# astabil.net
KiCad netlist of a schematic drawn in EAGLE
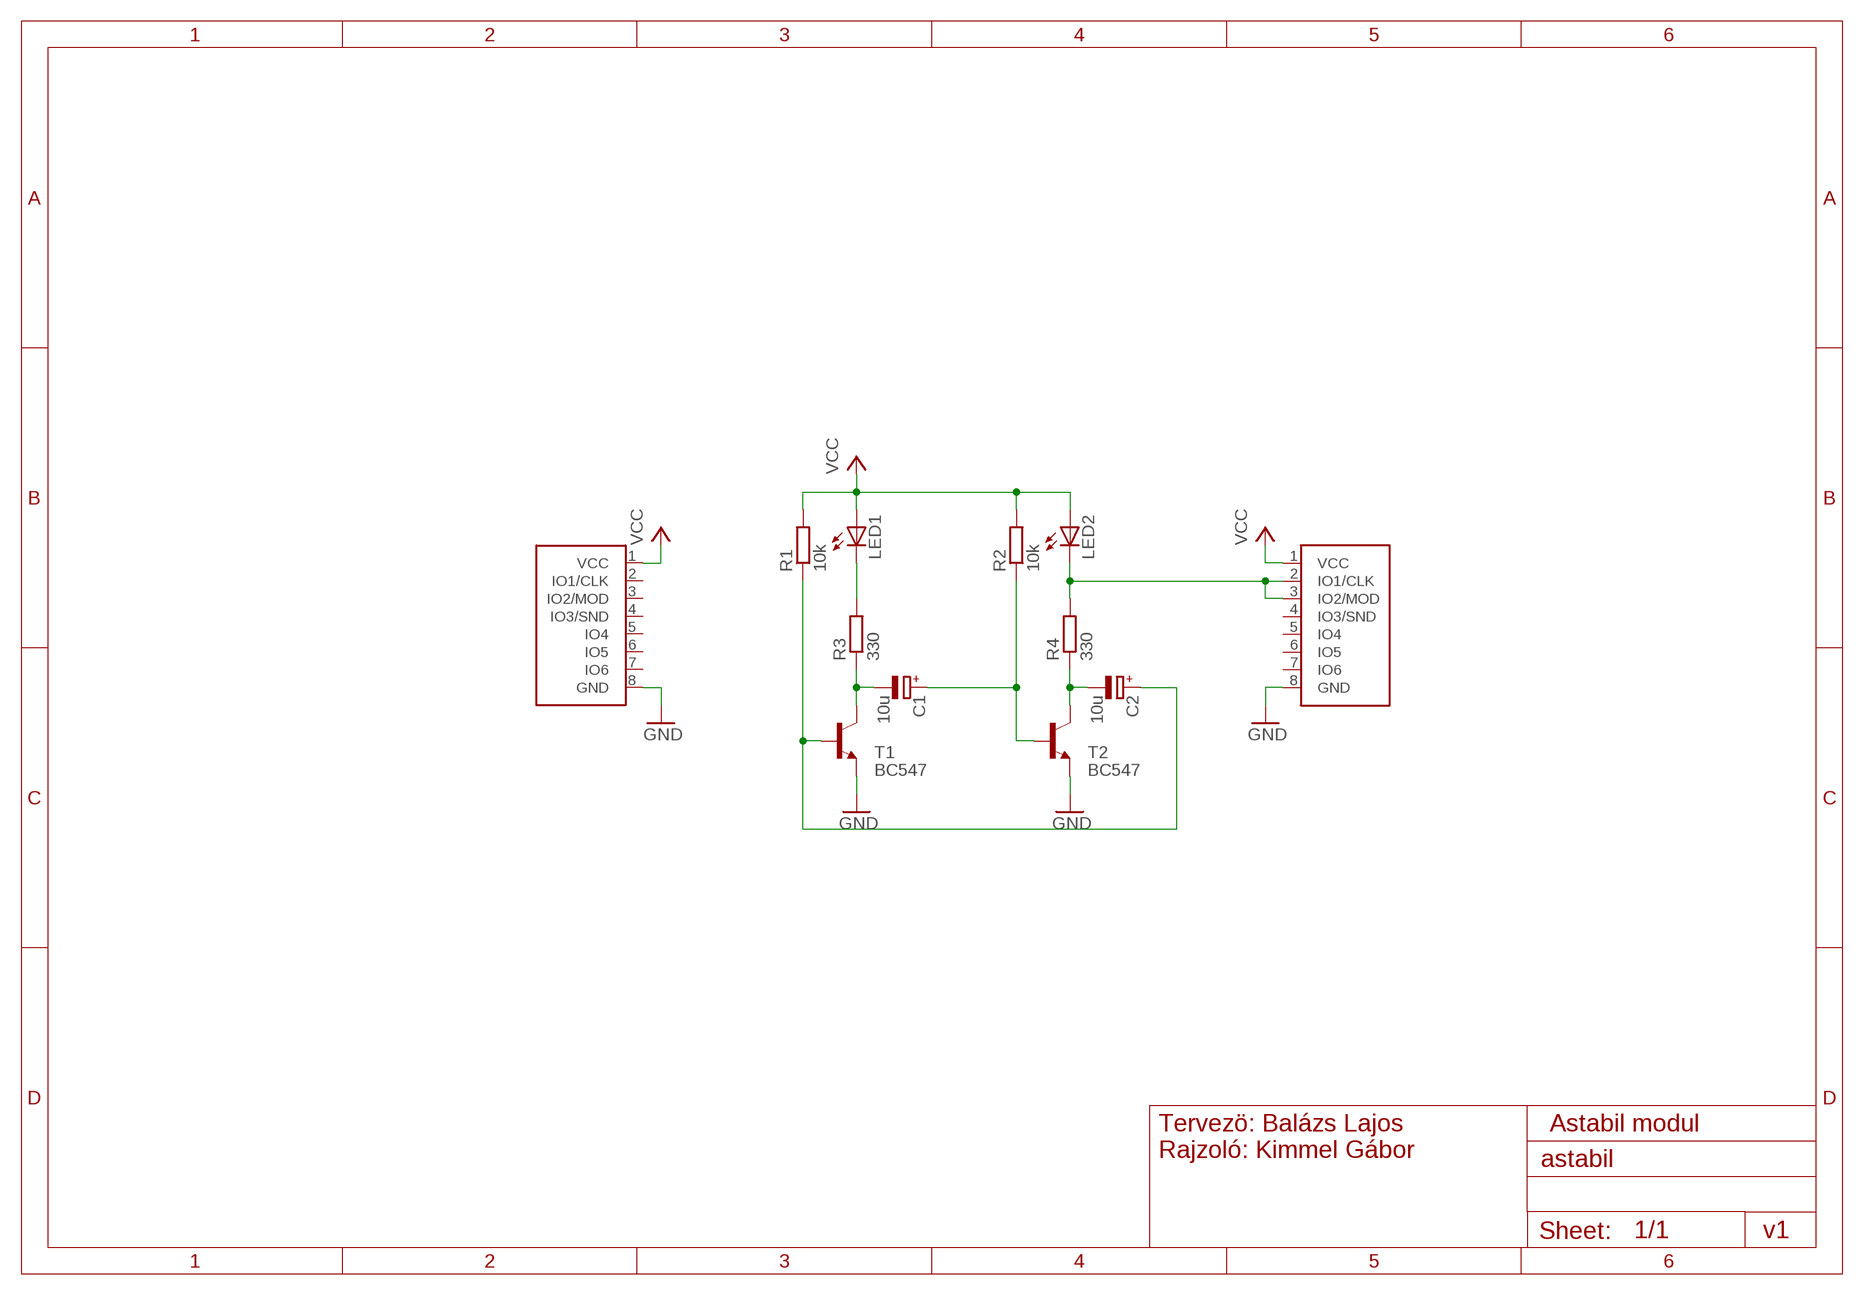
[diagram p0: schematic, sheet 1]

(export (version "E")
  (design (tool "Eeschema 10.0.6"))
  (components
    (comp (ref "C1")
      (value "10u")
      (footprint "eagle-import:E3,5-8")
      (libsource (lib "eagle-import") (part "CPOL-EUE3.5-8"))
    )
    (comp (ref "C2")
      (value "10u")
      (footprint "eagle-import:E3,5-8")
      (libsource (lib "eagle-import") (part "CPOL-EUE3.5-8"))
    )
    (comp (ref "LED1")
      (value "LED5MM")
      (footprint "eagle-import:LED5MM")
      (libsource (lib "eagle-import") (part "LED5MM"))
    )
    (comp (ref "LED2")
      (value "LED5MM")
      (footprint "eagle-import:LED5MM")
      (libsource (lib "eagle-import") (part "LED5MM"))
    )
    (comp (ref "R1")
      (value "10k")
      (footprint "eagle-import:0207_10")
      (libsource (lib "eagle-import") (part "R-EU_0207/10"))
    )
    (comp (ref "R2")
      (value "10k")
      (footprint "eagle-import:0207_10")
      (libsource (lib "eagle-import") (part "R-EU_0207/10"))
    )
    (comp (ref "R3")
      (value "330")
      (footprint "eagle-import:0207_10")
      (libsource (lib "eagle-import") (part "R-EU_0207/10"))
    )
    (comp (ref "R4")
      (value "330")
      (footprint "eagle-import:0207_10")
      (libsource (lib "eagle-import") (part "R-EU_0207/10"))
    )
    (comp (ref "T1")
      (value "BC547")
      (footprint "eagle-import:TO92-CBE")
      (libsource (lib "eagle-import") (part "-NPN-TO92-CBEBC547"))
    )
    (comp (ref "T2")
      (value "BC547")
      (footprint "eagle-import:TO92-CBE")
      (libsource (lib "eagle-import") (part "-NPN-TO92-CBEBC547"))
    )
    (comp (ref "U$1")
      (value "GANZ-CONNECTOR")
      (footprint "eagle-import:FE08W")
      (libsource (lib "eagle-import") (part "GANZ-CONNECTOR"))
    )
    (comp (ref "U$2")
      (value "GANZ-CONNECTOR-OUT")
      (footprint "eagle-import:MA08-1W")
      (libsource (lib "eagle-import") (part "GANZ-CONNECTOR-OUT"))
    )
  )
  (nets
    (net (code "1") (name "GND") (class "Default")
      (node (ref "T1") (pin "E") (pinfunction "E_E") (pintype "passive"))
      (node (ref "T2") (pin "E") (pinfunction "E_E") (pintype "passive"))
      (node (ref "U$1") (pin "8") (pinfunction "GND_8") (pintype "bidirectional"))
      (node (ref "U$2") (pin "8") (pinfunction "GND_8") (pintype "bidirectional"))
    )
    (net (code "2") (name "Net-(C1-Pad+)") (class "Default")
      (node (ref "C1") (pin "+") (pinfunction "+_+") (pintype "passive"))
      (node (ref "R2") (pin "1") (pinfunction "1_1") (pintype "passive"))
      (node (ref "T2") (pin "B") (pinfunction "B_B") (pintype "passive"))
    )
    (net (code "3") (name "Net-(C1-Pad-)") (class "Default")
      (node (ref "C1") (pin "-") (pinfunction "-_-") (pintype "passive"))
      (node (ref "R3") (pin "1") (pinfunction "1_1") (pintype "passive"))
      (node (ref "T1") (pin "C") (pinfunction "C_C") (pintype "passive"))
    )
    (net (code "4") (name "Net-(C2-Pad+)") (class "Default")
      (node (ref "C2") (pin "+") (pinfunction "+_+") (pintype "passive"))
      (node (ref "R1") (pin "1") (pinfunction "1_1") (pintype "passive"))
      (node (ref "T1") (pin "B") (pinfunction "B_B") (pintype "passive"))
    )
    (net (code "5") (name "Net-(C2-Pad-)") (class "Default")
      (node (ref "C2") (pin "-") (pinfunction "-_-") (pintype "passive"))
      (node (ref "R4") (pin "1") (pinfunction "1_1") (pintype "passive"))
      (node (ref "T2") (pin "C") (pinfunction "C_C") (pintype "passive"))
    )
    (net (code "6") (name "Net-(LED1-C)") (class "Default")
      (node (ref "LED1") (pin "K") (pinfunction "C_K") (pintype "passive"))
      (node (ref "R3") (pin "2") (pinfunction "2_2") (pintype "passive"))
    )
    (net (code "7") (name "Net-(LED2-C)") (class "Default")
      (node (ref "LED2") (pin "K") (pinfunction "C_K") (pintype "passive"))
      (node (ref "R4") (pin "2") (pinfunction "2_2") (pintype "passive"))
      (node (ref "U$2") (pin "2") (pinfunction "IO1/CLK_2") (pintype "bidirectional"))
      (node (ref "U$2") (pin "3") (pinfunction "IO2/MOD_3") (pintype "bidirectional"))
    )
    (net (code "8") (name "VCC") (class "Default")
      (node (ref "LED1") (pin "A") (pinfunction "A_A") (pintype "passive"))
      (node (ref "LED2") (pin "A") (pinfunction "A_A") (pintype "passive"))
      (node (ref "R1") (pin "2") (pinfunction "2_2") (pintype "passive"))
      (node (ref "R2") (pin "2") (pinfunction "2_2") (pintype "passive"))
      (node (ref "U$1") (pin "1") (pinfunction "VCC_1") (pintype "bidirectional"))
      (node (ref "U$2") (pin "1") (pinfunction "VCC_1") (pintype "bidirectional"))
    )
    (net (code "9") (name "unconnected-(U$1-IO1{slash}CLK-Pad2)") (class "Default")
      (node (ref "U$1") (pin "2") (pinfunction "IO1/CLK_2") (pintype "bidirectional"))
    )
    (net (code "10") (name "unconnected-(U$1-IO2{slash}MOD-Pad3)") (class "Default")
      (node (ref "U$1") (pin "3") (pinfunction "IO2/MOD_3") (pintype "bidirectional"))
    )
    (net (code "11") (name "unconnected-(U$1-IO3{slash}SND-Pad4)") (class "Default")
      (node (ref "U$1") (pin "4") (pinfunction "IO3/SND_4") (pintype "bidirectional"))
    )
    (net (code "12") (name "unconnected-(U$1-IO4-Pad5)") (class "Default")
      (node (ref "U$1") (pin "5") (pinfunction "IO4_5") (pintype "bidirectional"))
    )
    (net (code "13") (name "unconnected-(U$1-IO5-Pad6)") (class "Default")
      (node (ref "U$1") (pin "6") (pinfunction "IO5_6") (pintype "bidirectional"))
    )
    (net (code "14") (name "unconnected-(U$1-IO6-Pad7)") (class "Default")
      (node (ref "U$1") (pin "7") (pinfunction "IO6_7") (pintype "bidirectional"))
    )
    (net (code "15") (name "unconnected-(U$2-IO3{slash}SND-Pad4)") (class "Default")
      (node (ref "U$2") (pin "4") (pinfunction "IO3/SND_4") (pintype "bidirectional"))
    )
    (net (code "16") (name "unconnected-(U$2-IO4-Pad5)") (class "Default")
      (node (ref "U$2") (pin "5") (pinfunction "IO4_5") (pintype "bidirectional"))
    )
    (net (code "17") (name "unconnected-(U$2-IO5-Pad6)") (class "Default")
      (node (ref "U$2") (pin "6") (pinfunction "IO5_6") (pintype "bidirectional"))
    )
    (net (code "18") (name "unconnected-(U$2-IO6-Pad7)") (class "Default")
      (node (ref "U$2") (pin "7") (pinfunction "IO6_7") (pintype "bidirectional"))
    )
  )
)
